# salsa_II_v3a.net
KiCad netlist of a schematic drawn in EAGLE
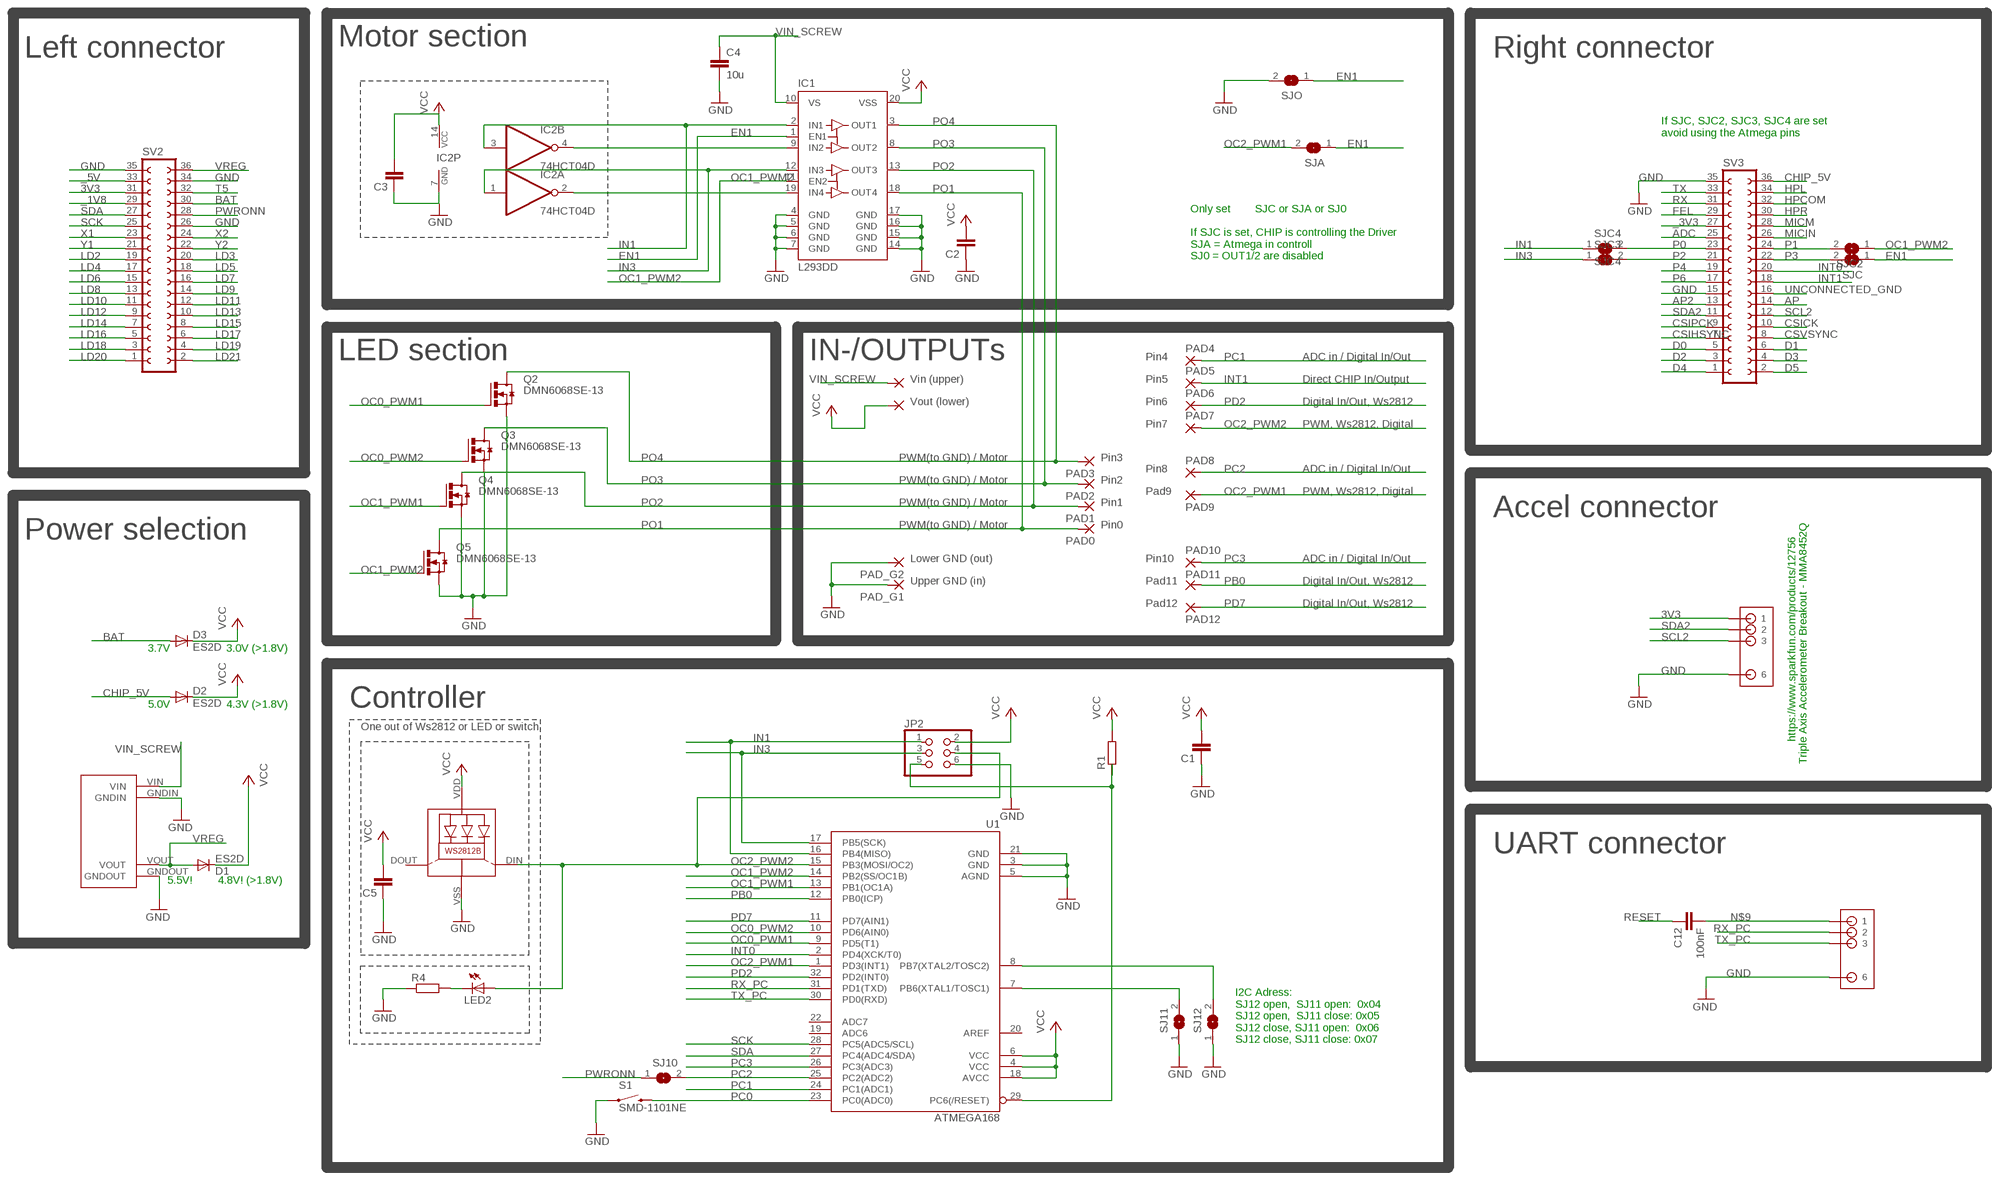
[diagram p0: schematic, sheet 1]

(export (version "E")
  (design (tool "Eeschema 10.0.6"))
  (components
    (comp (ref "C1")
      (value "C-EUC0805")
      (footprint "eagle-import:C0805")
      (libsource (lib "eagle-import") (part "C-EUC0805"))
    )
    (comp (ref "C2")
      (value "C-EUC0805")
      (footprint "eagle-import:C0805")
      (libsource (lib "eagle-import") (part "C-EUC0805"))
    )
    (comp (ref "C3")
      (value "C-EUC0805")
      (footprint "eagle-import:C0805")
      (libsource (lib "eagle-import") (part "C-EUC0805"))
    )
    (comp (ref "C4")
      (value "10u")
      (footprint "eagle-import:C1210")
      (libsource (lib "eagle-import") (part "C-EUC1210"))
    )
    (comp (ref "C5")
      (value "C-EUC0805")
      (footprint "eagle-import:C0805")
      (libsource (lib "eagle-import") (part "C-EUC0805"))
    )
    (comp (ref "C12")
      (value "100nF")
      (footprint "eagle-import:C1206")
      (libsource (lib "eagle-import") (part "C-EUC1206"))
    )
    (comp (ref "D1")
      (value "ES2D")
      (footprint "eagle-import:SMB")
      (libsource (lib "eagle-import") (part "ES2D"))
    )
    (comp (ref "D2")
      (value "ES2D")
      (footprint "eagle-import:SMB")
      (libsource (lib "eagle-import") (part "ES2D"))
    )
    (comp (ref "D3")
      (value "ES2D")
      (footprint "eagle-import:SMB")
      (libsource (lib "eagle-import") (part "ES2D"))
    )
    (comp (ref "IC1")
      (value "L293DD")
      (footprint "eagle-import:SO20")
      (libsource (lib "eagle-import") (part "L293DD"))
    )
    (comp (ref "IC2")
      (value "74HCT04D")
      (footprint "eagle-import:SO14")
      (libsource (lib "eagle-import") (part "7404DHCT"))
    )
    (comp (ref "JP2")
      (value "PINHD-2X3")
      (footprint "eagle-import:2X03")
      (libsource (lib "eagle-import") (part "PINHD-2X3"))
    )
    (comp (ref "LED1")
      (value "WS2812B")
      (footprint "eagle-import:WS2812B")
      (libsource (lib "eagle-import") (part "WS2812B"))
    )
    (comp (ref "LED2")
      (value "LEDCHIP-LED0805")
      (footprint "eagle-import:CHIP-LED0805")
      (libsource (lib "eagle-import") (part "LEDCHIP-LED0805"))
    )
    (comp (ref "PAD0")
      (value "3,17/1,3")
      (footprint "eagle-import:3,17_1,3")
      (libsource (lib "eagle-import") (part "3,17/1,3"))
    )
    (comp (ref "PAD1")
      (value "3,17/1,3")
      (footprint "eagle-import:3,17_1,3")
      (libsource (lib "eagle-import") (part "3,17/1,3"))
    )
    (comp (ref "PAD2")
      (value "3,17/1,3")
      (footprint "eagle-import:3,17_1,3")
      (libsource (lib "eagle-import") (part "3,17/1,3"))
    )
    (comp (ref "PAD3")
      (value "3,17/1,3")
      (footprint "eagle-import:3,17_1,3")
      (libsource (lib "eagle-import") (part "3,17/1,3"))
    )
    (comp (ref "PAD4")
      (value "3,17/1,3")
      (footprint "eagle-import:3,17_1,3")
      (libsource (lib "eagle-import") (part "3,17/1,3"))
    )
    (comp (ref "PAD5")
      (value "3,17/1,3")
      (footprint "eagle-import:3,17_1,3")
      (libsource (lib "eagle-import") (part "3,17/1,3"))
    )
    (comp (ref "PAD6")
      (value "3,17/1,3")
      (footprint "eagle-import:3,17_1,3")
      (libsource (lib "eagle-import") (part "3,17/1,3"))
    )
    (comp (ref "PAD7")
      (value "3,17/1,3")
      (footprint "eagle-import:3,17_1,3")
      (libsource (lib "eagle-import") (part "3,17/1,3"))
    )
    (comp (ref "PAD8")
      (value "3,17/1,3")
      (footprint "eagle-import:3,17_1,3")
      (libsource (lib "eagle-import") (part "3,17/1,3"))
    )
    (comp (ref "PAD9")
      (value "SMD2")
      (footprint "eagle-import:SMD1,27-2,54")
      (libsource (lib "eagle-import") (part "SMD2"))
    )
    (comp (ref "PAD10")
      (value "3,17/1,3")
      (footprint "eagle-import:3,17_1,3")
      (libsource (lib "eagle-import") (part "3,17/1,3"))
    )
    (comp (ref "PAD11")
      (value "WIREPADSMD1,27-254")
      (footprint "eagle-import:SMD1,27-2,54")
      (libsource (lib "eagle-import") (part "WIREPADSMD1,27-254"))
    )
    (comp (ref "PAD12")
      (value "SMD2")
      (footprint "eagle-import:SMD1,27-2,54")
      (libsource (lib "eagle-import") (part "SMD2"))
    )
    (comp (ref "PAD17")
      (value "3,17/1,3")
      (footprint "eagle-import:3,17_1,3")
      (libsource (lib "eagle-import") (part "3,17/1,3"))
    )
    (comp (ref "PAD_G1")
      (value "3,17/1,3")
      (footprint "eagle-import:3,17_1,3")
      (libsource (lib "eagle-import") (part "3,17/1,3"))
    )
    (comp (ref "PAD_G2")
      (value "3,17/1,3")
      (footprint "eagle-import:3,17_1,3")
      (libsource (lib "eagle-import") (part "3,17/1,3"))
    )
    (comp (ref "PAD_VIN")
      (value "3,17/1,3")
      (footprint "eagle-import:3,17_1,3")
      (libsource (lib "eagle-import") (part "3,17/1,3"))
    )
    (comp (ref "Q2")
      (value "DMN6068SE-13")
      (footprint "eagle-import:SOT223")
      (libsource (lib "eagle-import") (part "NMOSFET_SMD_223"))
    )
    (comp (ref "Q3")
      (value "DMN6068SE-13")
      (footprint "eagle-import:SOT223")
      (libsource (lib "eagle-import") (part "NMOSFET_SMD_223"))
    )
    (comp (ref "Q4")
      (value "DMN6068SE-13")
      (footprint "eagle-import:SOT223")
      (libsource (lib "eagle-import") (part "NMOSFET_SMD_223"))
    )
    (comp (ref "Q5")
      (value "DMN6068SE-13")
      (footprint "eagle-import:SOT223")
      (libsource (lib "eagle-import") (part "NMOSFET_SMD_223"))
    )
    (comp (ref "R1")
      (value "R-EU_M1206")
      (footprint "eagle-import:M1206")
      (libsource (lib "eagle-import") (part "R-EU_M1206"))
    )
    (comp (ref "R4")
      (value "R-EU_M1206")
      (footprint "eagle-import:M1206")
      (libsource (lib "eagle-import") (part "R-EU_M1206"))
    )
    (comp (ref "S1")
      (value "SMD-1101NE")
      (footprint "eagle-import:TACTILE-SWITCH-1101NE")
      (libsource (lib "eagle-import") (part "SWITCH-MOMENTARY-2-SMD-1101NE"))
    )
    (comp (ref "SJ10")
      (value "SJ")
      (footprint "eagle-import:SJ")
      (libsource (lib "eagle-import") (part "SJ"))
    )
    (comp (ref "SJ11")
      (value "SJ")
      (footprint "eagle-import:SJ")
      (libsource (lib "eagle-import") (part "SJ"))
    )
    (comp (ref "SJ12")
      (value "SJ")
      (footprint "eagle-import:SJ")
      (libsource (lib "eagle-import") (part "SJ"))
    )
    (comp (ref "SJA") (value "SJ") (footprint "eagle-import:SJ") (libsource (lib "eagle-import") (part "SJ")))
    (comp (ref "SJC") (value "SJ") (footprint "eagle-import:SJ") (libsource (lib "eagle-import") (part "SJ")))
    (comp (ref "SJC2")
      (value "SJ")
      (footprint "eagle-import:SJ")
      (libsource (lib "eagle-import") (part "SJ"))
    )
    (comp (ref "SJC3")
      (value "SJ")
      (footprint "eagle-import:SJ")
      (libsource (lib "eagle-import") (part "SJ"))
    )
    (comp (ref "SJC4")
      (value "SJC4")
      (footprint "eagle-import:SJ")
      (libsource (lib "eagle-import") (part "SJ"))
    )
    (comp (ref "SJO") (value "SJ") (footprint "eagle-import:SJ") (libsource (lib "eagle-import") (part "SJ")))
    (comp (ref "SV2")
      (value "FE18-2")
      (footprint "eagle-import:FE18-2")
      (libsource (lib "eagle-import") (part "FE18-2"))
    )
    (comp (ref "SV3")
      (value "FE18-2")
      (footprint "eagle-import:FE18-2")
      (libsource (lib "eagle-import") (part "FE18-2"))
    )
    (comp (ref "U$1")
      (value "MP1584EN")
      (footprint "eagle-import:MP1584EN")
      (libsource (lib "eagle-import") (part "MP1584EN"))
    )
    (comp (ref "U$3")
      (value "6_TO_4_HEADER")
      (footprint "eagle-import:6_TO_4_HEADER")
      (libsource (lib "eagle-import") (part "6_TO_4_HEADER"))
    )
    (comp (ref "U$4")
      (value "6_TO_4_HEADER")
      (footprint "eagle-import:6_TO_4_HEADER")
      (libsource (lib "eagle-import") (part "6_TO_4_HEADER"))
    )
    (comp (ref "U1")
      (value "ATMEGA168")
      (footprint "eagle-import:TQFP32-08")
      (libsource (lib "eagle-import") (part "ATMEGA168"))
    )
  )
  (nets
    (net (code "1") (name "/3V3") (class "Default")
      (node (ref "SV2") (pin "31") (pinfunction "31_31") (pintype "passive"))
      (node (ref "U$4") (pin "1") (pinfunction "1_1") (pintype "bidirectional"))
    )
    (net (code "2") (name "/ADC") (class "Default")
      (node (ref "SV3") (pin "25") (pinfunction "25_25") (pintype "passive"))
    )
    (net (code "3") (name "/AP") (class "Default")
      (node (ref "SV3") (pin "14") (pinfunction "14_14") (pintype "passive"))
    )
    (net (code "4") (name "/AP2") (class "Default")
      (node (ref "SV3") (pin "13") (pinfunction "13_13") (pintype "passive"))
    )
    (net (code "5") (name "/BAT") (class "Default")
      (node (ref "D3") (pin "A") (pinfunction "A_A") (pintype "passive"))
      (node (ref "SV2") (pin "30") (pinfunction "30_30") (pintype "passive"))
    )
    (net (code "6") (name "/CHIP_5V") (class "Default")
      (node (ref "D2") (pin "A") (pinfunction "A_A") (pintype "passive"))
      (node (ref "SV3") (pin "36") (pinfunction "36_36") (pintype "passive"))
    )
    (net (code "7") (name "/CSICK") (class "Default")
      (node (ref "SV3") (pin "10") (pinfunction "10_10") (pintype "passive"))
    )
    (net (code "8") (name "/CSIHSYNC") (class "Default")
      (node (ref "SV3") (pin "7") (pinfunction "7_7") (pintype "passive"))
    )
    (net (code "9") (name "/CSIPCK") (class "Default")
      (node (ref "SV3") (pin "9") (pinfunction "9_9") (pintype "passive"))
    )
    (net (code "10") (name "/CSVSYNC") (class "Default")
      (node (ref "SV3") (pin "8") (pinfunction "8_8") (pintype "passive"))
    )
    (net (code "11") (name "/D0") (class "Default")
      (node (ref "SV3") (pin "5") (pinfunction "5_5") (pintype "passive"))
    )
    (net (code "12") (name "/D1") (class "Default")
      (node (ref "SV3") (pin "6") (pinfunction "6_6") (pintype "passive"))
    )
    (net (code "13") (name "/D2") (class "Default")
      (node (ref "SV3") (pin "3") (pinfunction "3_3") (pintype "passive"))
    )
    (net (code "14") (name "/D3") (class "Default")
      (node (ref "SV3") (pin "4") (pinfunction "4_4") (pintype "passive"))
    )
    (net (code "15") (name "/D4") (class "Default")
      (node (ref "SV3") (pin "1") (pinfunction "1_1") (pintype "passive"))
    )
    (net (code "16") (name "/D5") (class "Default")
      (node (ref "SV3") (pin "2") (pinfunction "2_2") (pintype "passive"))
    )
    (net (code "17") (name "/EN1") (class "Default")
      (node (ref "IC1") (pin "1") (pinfunction "EN1_1") (pintype "input"))
      (node (ref "SJA") (pin "1") (pinfunction "1_1") (pintype "passive"))
      (node (ref "SJC") (pin "1") (pinfunction "1_1") (pintype "passive"))
      (node (ref "SJO") (pin "1") (pinfunction "1_1") (pintype "passive"))
    )
    (net (code "18") (name "/FEL") (class "Default")
      (node (ref "SV3") (pin "29") (pinfunction "29_29") (pintype "passive"))
    )
    (net (code "19") (name "/HPCOM") (class "Default")
      (node (ref "SV3") (pin "32") (pinfunction "32_32") (pintype "passive"))
    )
    (net (code "20") (name "/HPL") (class "Default")
      (node (ref "SV3") (pin "34") (pinfunction "34_34") (pintype "passive"))
    )
    (net (code "21") (name "/HPR") (class "Default")
      (node (ref "SV3") (pin "30") (pinfunction "30_30") (pintype "passive"))
    )
    (net (code "22") (name "/IN1") (class "Default")
      (node (ref "IC1") (pin "2") (pinfunction "IN1_2") (pintype "input"))
      (node (ref "IC2") (pin "3") (pinfunction "I_3") (pintype "input"))
      (node (ref "JP2") (pin "1") (pinfunction "1_1") (pintype "passive"))
      (node (ref "SJC4") (pin "1") (pinfunction "1_1") (pintype "passive"))
      (node (ref "U1") (pin "16") (pinfunction "PB4(MISO)_16") (pintype "bidirectional"))
    )
    (net (code "23") (name "/IN3") (class "Default")
      (node (ref "IC1") (pin "12") (pinfunction "IN3_12") (pintype "input"))
      (node (ref "IC2") (pin "1") (pinfunction "I_1") (pintype "input"))
      (node (ref "JP2") (pin "3") (pinfunction "3_3") (pintype "passive"))
      (node (ref "SJC3") (pin "1") (pinfunction "1_1") (pintype "passive"))
      (node (ref "U1") (pin "17") (pinfunction "PB5(SCK)_17") (pintype "bidirectional"))
    )
    (net (code "24") (name "/INT0") (class "Default")
      (node (ref "SV3") (pin "20") (pinfunction "20_20") (pintype "passive"))
      (node (ref "U1") (pin "2") (pinfunction "PD4(XCK/T0)_2") (pintype "bidirectional"))
    )
    (net (code "25") (name "/INT1") (class "Default")
      (node (ref "PAD5") (pin "1") (pinfunction "P_1") (pintype "passive"))
      (node (ref "SV3") (pin "18") (pinfunction "18_18") (pintype "passive"))
    )
    (net (code "26") (name "/LD2") (class "Default")
      (node (ref "SV2") (pin "19") (pinfunction "19_19") (pintype "passive"))
    )
    (net (code "27") (name "/LD3") (class "Default")
      (node (ref "SV2") (pin "20") (pinfunction "20_20") (pintype "passive"))
    )
    (net (code "28") (name "/LD4") (class "Default")
      (node (ref "SV2") (pin "17") (pinfunction "17_17") (pintype "passive"))
    )
    (net (code "29") (name "/LD5") (class "Default")
      (node (ref "SV2") (pin "18") (pinfunction "18_18") (pintype "passive"))
    )
    (net (code "30") (name "/LD6") (class "Default")
      (node (ref "SV2") (pin "15") (pinfunction "15_15") (pintype "passive"))
    )
    (net (code "31") (name "/LD7") (class "Default")
      (node (ref "SV2") (pin "16") (pinfunction "16_16") (pintype "passive"))
    )
    (net (code "32") (name "/LD8") (class "Default")
      (node (ref "SV2") (pin "13") (pinfunction "13_13") (pintype "passive"))
    )
    (net (code "33") (name "/LD9") (class "Default")
      (node (ref "SV2") (pin "14") (pinfunction "14_14") (pintype "passive"))
    )
    (net (code "34") (name "/LD10") (class "Default")
      (node (ref "SV2") (pin "11") (pinfunction "11_11") (pintype "passive"))
    )
    (net (code "35") (name "/LD11") (class "Default")
      (node (ref "SV2") (pin "12") (pinfunction "12_12") (pintype "passive"))
    )
    (net (code "36") (name "/LD12") (class "Default")
      (node (ref "SV2") (pin "9") (pinfunction "9_9") (pintype "passive"))
    )
    (net (code "37") (name "/LD13") (class "Default")
      (node (ref "SV2") (pin "10") (pinfunction "10_10") (pintype "passive"))
    )
    (net (code "38") (name "/LD14") (class "Default")
      (node (ref "SV2") (pin "7") (pinfunction "7_7") (pintype "passive"))
    )
    (net (code "39") (name "/LD15") (class "Default")
      (node (ref "SV2") (pin "8") (pinfunction "8_8") (pintype "passive"))
    )
    (net (code "40") (name "/LD16") (class "Default")
      (node (ref "SV2") (pin "5") (pinfunction "5_5") (pintype "passive"))
    )
    (net (code "41") (name "/LD17") (class "Default")
      (node (ref "SV2") (pin "6") (pinfunction "6_6") (pintype "passive"))
    )
    (net (code "42") (name "/LD18") (class "Default")
      (node (ref "SV2") (pin "3") (pinfunction "3_3") (pintype "passive"))
    )
    (net (code "43") (name "/LD19") (class "Default")
      (node (ref "SV2") (pin "4") (pinfunction "4_4") (pintype "passive"))
    )
    (net (code "44") (name "/LD20") (class "Default")
      (node (ref "SV2") (pin "1") (pinfunction "1_1") (pintype "passive"))
    )
    (net (code "45") (name "/LD21") (class "Default")
      (node (ref "SV2") (pin "2") (pinfunction "2_2") (pintype "passive"))
    )
    (net (code "46") (name "/MICIN") (class "Default")
      (node (ref "SV3") (pin "26") (pinfunction "26_26") (pintype "passive"))
    )
    (net (code "47") (name "/MICM") (class "Default")
      (node (ref "SV3") (pin "28") (pinfunction "28_28") (pintype "passive"))
    )
    (net (code "48") (name "/N$9") (class "Default")
      (node (ref "C12") (pin "2") (pinfunction "2_2") (pintype "passive"))
      (node (ref "U$3") (pin "1") (pinfunction "1_1") (pintype "bidirectional"))
    )
    (net (code "49") (name "/OC0_PWM1") (class "Default")
      (node (ref "Q2") (pin "1") (pinfunction "G_1") (pintype "passive"))
      (node (ref "U1") (pin "9") (pinfunction "PD5(T1)_9") (pintype "bidirectional"))
    )
    (net (code "50") (name "/OC0_PWM2") (class "Default")
      (node (ref "Q3") (pin "1") (pinfunction "G_1") (pintype "passive"))
      (node (ref "U1") (pin "10") (pinfunction "PD6(AIN0)_10") (pintype "bidirectional"))
    )
    (net (code "51") (name "/OC1_PWM1") (class "Default")
      (node (ref "Q4") (pin "1") (pinfunction "G_1") (pintype "passive"))
      (node (ref "U1") (pin "13") (pinfunction "PB1(OC1A)_13") (pintype "bidirectional"))
    )
    (net (code "52") (name "/OC1_PWM2") (class "Default")
      (node (ref "IC1") (pin "11") (pinfunction "EN2_11") (pintype "input"))
      (node (ref "Q5") (pin "1") (pinfunction "G_1") (pintype "passive"))
      (node (ref "SJC2") (pin "1") (pinfunction "1_1") (pintype "passive"))
      (node (ref "U1") (pin "14") (pinfunction "PB2(SS/OC1B)_14") (pintype "bidirectional"))
    )
    (net (code "53") (name "/OC2_PWM1") (class "Default")
      (node (ref "PAD9") (pin "1") (pinfunction "P_1") (pintype "passive"))
      (node (ref "SJA") (pin "2") (pinfunction "2_2") (pintype "passive"))
      (node (ref "U1") (pin "1") (pinfunction "PD3(INT1)_1") (pintype "bidirectional"))
    )
    (net (code "54") (name "/OC2_PWM2") (class "Default")
      (node (ref "JP2") (pin "4") (pinfunction "4_4") (pintype "passive"))
      (node (ref "LED1") (pin "DIN") (pinfunction "DI_DIN") (pintype "input"))
      (node (ref "LED2") (pin "A") (pinfunction "A_A") (pintype "passive"))
      (node (ref "PAD7") (pin "1") (pinfunction "P_1") (pintype "passive"))
      (node (ref "U1") (pin "15") (pinfunction "PB3(MOSI/OC2)_15") (pintype "bidirectional"))
    )
    (net (code "55") (name "/P0") (class "Default")
      (node (ref "SJC4") (pin "2") (pinfunction "2_2") (pintype "passive"))
      (node (ref "SV3") (pin "23") (pinfunction "23_23") (pintype "passive"))
    )
    (net (code "56") (name "/P1") (class "Default")
      (node (ref "SJC2") (pin "2") (pinfunction "2_2") (pintype "passive"))
      (node (ref "SV3") (pin "24") (pinfunction "24_24") (pintype "passive"))
    )
    (net (code "57") (name "/P2") (class "Default")
      (node (ref "SJC3") (pin "2") (pinfunction "2_2") (pintype "passive"))
      (node (ref "SV3") (pin "21") (pinfunction "21_21") (pintype "passive"))
    )
    (net (code "58") (name "/P3") (class "Default")
      (node (ref "SJC") (pin "2") (pinfunction "2_2") (pintype "passive"))
      (node (ref "SV3") (pin "22") (pinfunction "22_22") (pintype "passive"))
    )
    (net (code "59") (name "/P4") (class "Default")
      (node (ref "SV3") (pin "19") (pinfunction "19_19") (pintype "passive"))
    )
    (net (code "60") (name "/P6") (class "Default")
      (node (ref "SV3") (pin "17") (pinfunction "17_17") (pintype "passive"))
    )
    (net (code "61") (name "/PB0") (class "Default")
      (node (ref "PAD11") (pin "1") (pinfunction "P_1") (pintype "passive"))
      (node (ref "U1") (pin "12") (pinfunction "PB0(ICP)_12") (pintype "bidirectional"))
    )
    (net (code "62") (name "/PC0") (class "Default")
      (node (ref "S1") (pin "P$2") (pinfunction "2_P$2") (pintype "passive"))
      (node (ref "U1") (pin "23") (pinfunction "PC0(ADC0)_23") (pintype "bidirectional"))
    )
    (net (code "63") (name "/PC1") (class "Default")
      (node (ref "PAD4") (pin "1") (pinfunction "P_1") (pintype "passive"))
      (node (ref "U1") (pin "24") (pinfunction "PC1(ADC1)_24") (pintype "bidirectional"))
    )
    (net (code "64") (name "/PC2") (class "Default")
      (node (ref "PAD8") (pin "1") (pinfunction "P_1") (pintype "passive"))
      (node (ref "SJ10") (pin "2") (pinfunction "2_2") (pintype "passive"))
      (node (ref "U1") (pin "25") (pinfunction "PC2(ADC2)_25") (pintype "bidirectional"))
    )
    (net (code "65") (name "/PC3") (class "Default")
      (node (ref "PAD10") (pin "1") (pinfunction "P_1") (pintype "passive"))
      (node (ref "U1") (pin "26") (pinfunction "PC3(ADC3)_26") (pintype "bidirectional"))
    )
    (net (code "66") (name "/PD2") (class "Default")
      (node (ref "PAD6") (pin "1") (pinfunction "P_1") (pintype "passive"))
      (node (ref "U1") (pin "32") (pinfunction "PD2(INT0)_32") (pintype "bidirectional"))
    )
    (net (code "67") (name "/PD7") (class "Default")
      (node (ref "PAD12") (pin "1") (pinfunction "P_1") (pintype "passive"))
      (node (ref "U1") (pin "11") (pinfunction "PD7(AIN1)_11") (pintype "bidirectional"))
    )
    (net (code "68") (name "/PO1") (class "Default")
      (node (ref "IC1") (pin "18") (pinfunction "OUT4_18") (pintype "output"))
      (node (ref "PAD0") (pin "1") (pinfunction "P_1") (pintype "passive"))
      (node (ref "Q5") (pin "2") (pinfunction "D_2") (pintype "passive"))
      (node (ref "Q5") (pin "4") (pinfunction "D_4") (pintype "passive"))
    )
    (net (code "69") (name "/PO2") (class "Default")
      (node (ref "IC1") (pin "13") (pinfunction "OUT3_13") (pintype "output"))
      (node (ref "PAD1") (pin "1") (pinfunction "P_1") (pintype "passive"))
      (node (ref "Q4") (pin "2") (pinfunction "D_2") (pintype "passive"))
      (node (ref "Q4") (pin "4") (pinfunction "D_4") (pintype "passive"))
    )
    (net (code "70") (name "/PO3") (class "Default")
      (node (ref "IC1") (pin "8") (pinfunction "OUT2_8") (pintype "output"))
      (node (ref "PAD2") (pin "1") (pinfunction "P_1") (pintype "passive"))
      (node (ref "Q3") (pin "2") (pinfunction "D_2") (pintype "passive"))
      (node (ref "Q3") (pin "4") (pinfunction "D_4") (pintype "passive"))
    )
    (net (code "71") (name "/PO4") (class "Default")
      (node (ref "IC1") (pin "3") (pinfunction "OUT1_3") (pintype "output"))
      (node (ref "PAD3") (pin "1") (pinfunction "P_1") (pintype "passive"))
      (node (ref "Q2") (pin "2") (pinfunction "D_2") (pintype "passive"))
      (node (ref "Q2") (pin "4") (pinfunction "D_4") (pintype "passive"))
    )
    (net (code "72") (name "/PWRONN") (class "Default")
      (node (ref "SJ10") (pin "1") (pinfunction "1_1") (pintype "passive"))
      (node (ref "SV2") (pin "28") (pinfunction "28_28") (pintype "passive"))
    )
    (net (code "73") (name "/RESET") (class "Default")
      (node (ref "C12") (pin "1") (pinfunction "1_1") (pintype "passive"))
      (node (ref "JP2") (pin "5") (pinfunction "5_5") (pintype "passive"))
      (node (ref "R1") (pin "1") (pinfunction "1_1") (pintype "passive"))
      (node (ref "U1") (pin "29") (pinfunction "PC6(/RESET)_29") (pintype "bidirectional"))
    )
    (net (code "74") (name "/RX") (class "Default")
      (node (ref "SV3") (pin "31") (pinfunction "31_31") (pintype "passive"))
    )
    (net (code "75") (name "/RX_PC") (class "Default")
      (node (ref "U$3") (pin "2") (pinfunction "2_2") (pintype "bidirectional"))
      (node (ref "U1") (pin "31") (pinfunction "PD1(TXD)_31") (pintype "bidirectional"))
    )
    (net (code "76") (name "/SCK") (class "Default")
      (node (ref "SV2") (pin "25") (pinfunction "25_25") (pintype "passive"))
      (node (ref "U1") (pin "28") (pinfunction "PC5(ADC5/SCL)_28") (pintype "bidirectional"))
    )
    (net (code "77") (name "/SCL2") (class "Default")
      (node (ref "SV3") (pin "12") (pinfunction "12_12") (pintype "passive"))
      (node (ref "U$4") (pin "3") (pinfunction "3_3") (pintype "bidirectional"))
    )
    (net (code "78") (name "/SDA") (class "Default")
      (node (ref "SV2") (pin "27") (pinfunction "27_27") (pintype "passive"))
      (node (ref "U1") (pin "27") (pinfunction "PC4(ADC4/SDA)_27") (pintype "bidirectional"))
    )
    (net (code "79") (name "/SDA2") (class "Default")
      (node (ref "SV3") (pin "11") (pinfunction "11_11") (pintype "passive"))
      (node (ref "U$4") (pin "2") (pinfunction "2_2") (pintype "bidirectional"))
    )
    (net (code "80") (name "/T5") (class "Default")
      (node (ref "SV2") (pin "32") (pinfunction "32_32") (pintype "passive"))
    )
    (net (code "81") (name "/TX") (class "Default")
      (node (ref "SV3") (pin "33") (pinfunction "33_33") (pintype "passive"))
    )
    (net (code "82") (name "/TX_PC") (class "Default")
      (node (ref "U$3") (pin "3") (pinfunction "3_3") (pintype "bidirectional"))
      (node (ref "U1") (pin "30") (pinfunction "PD0(RXD)_30") (pintype "bidirectional"))
    )
    (net (code "83") (name "/UNCONNECTED_GND") (class "Default")
      (node (ref "SV3") (pin "16") (pinfunction "16_16") (pintype "passive"))
    )
    (net (code "84") (name "/VIN_SCREW") (class "Default")
      (node (ref "C4") (pin "1") (pinfunction "1_1") (pintype "passive"))
      (node (ref "IC1") (pin "10") (pinfunction "VS_10") (pintype "power_in"))
      (node (ref "PAD_VIN") (pin "1") (pinfunction "P_1") (pintype "passive"))
      (node (ref "U$1") (pin "VIN") (pinfunction "VIN_VIN") (pintype "power_in"))
    )
    (net (code "85") (name "/VREG") (class "Default")
      (node (ref "D1") (pin "A") (pinfunction "A_A") (pintype "passive"))
      (node (ref "SV2") (pin "36") (pinfunction "36_36") (pintype "passive"))
      (node (ref "U$1") (pin "VOUT") (pinfunction "VOUT_VOUT") (pintype "power_in"))
    )
    (net (code "86") (name "/X1") (class "Default")
      (node (ref "SV2") (pin "23") (pinfunction "23_23") (pintype "passive"))
    )
    (net (code "87") (name "/X2") (class "Default")
      (node (ref "SV2") (pin "24") (pinfunction "24_24") (pintype "passive"))
    )
    (net (code "88") (name "/Y1") (class "Default")
      (node (ref "SV2") (pin "21") (pinfunction "21_21") (pintype "passive"))
    )
    (net (code "89") (name "/Y2") (class "Default")
      (node (ref "SV2") (pin "22") (pinfunction "22_22") (pintype "passive"))
    )
    (net (code "90") (name "/_1V8") (class "Default")
      (node (ref "SV2") (pin "29") (pinfunction "29_29") (pintype "passive"))
    )
    (net (code "91") (name "/_3V3") (class "Default")
      (node (ref "SV3") (pin "27") (pinfunction "27_27") (pintype "passive"))
    )
    (net (code "92") (name "/_5V") (class "Default")
      (node (ref "SV2") (pin "33") (pinfunction "33_33") (pintype "passive"))
    )
    (net (code "93") (name "GND") (class "Default")
      (node (ref "C1") (pin "1") (pinfunction "1_1") (pintype "passive"))
      (node (ref "C2") (pin "1") (pinfunction "1_1") (pintype "passive"))
      (node (ref "C3") (pin "1") (pinfunction "1_1") (pintype "passive"))
      (node (ref "C4") (pin "2") (pinfunction "2_2") (pintype "passive"))
      (node (ref "C5") (pin "1") (pinfunction "1_1") (pintype "passive"))
      (node (ref "IC1") (pin "14") (pinfunction "GND_14") (pintype "power_in"))
      (node (ref "IC1") (pin "15") (pinfunction "GND_15") (pintype "power_in"))
      (node (ref "IC1") (pin "16") (pinfunction "GND_16") (pintype "power_in"))
      (node (ref "IC1") (pin "17") (pinfunction "GND_17") (pintype "power_in"))
      (node (ref "IC1") (pin "4") (pinfunction "GND_4") (pintype "power_in"))
      (node (ref "IC1") (pin "5") (pinfunction "GND_5") (pintype "power_in"))
      (node (ref "IC1") (pin "6") (pinfunction "GND_6") (pintype "power_in"))
      (node (ref "IC1") (pin "7") (pinfunction "GND_7") (pintype "power_in"))
      (node (ref "IC2") (pin "7") (pinfunction "GND_7") (pintype "power_in"))
      (node (ref "JP2") (pin "6") (pinfunction "6_6") (pintype "passive"))
      (node (ref "LED1") (pin "VSS") (pinfunction "GND_VSS") (pintype "power_in"))
      (node (ref "PAD_G1") (pin "1") (pinfunction "P_1") (pintype "passive"))
      (node (ref "PAD_G2") (pin "1") (pinfunction "P_1") (pintype "passive"))
      (node (ref "Q2") (pin "3") (pinfunction "S_3") (pintype "passive"))
      (node (ref "Q3") (pin "3") (pinfunction "S_3") (pintype "passive"))
      (node (ref "Q4") (pin "3") (pinfunction "S_3") (pintype "passive"))
      (node (ref "Q5") (pin "3") (pinfunction "S_3") (pintype "passive"))
      (node (ref "R4") (pin "1") (pinfunction "1_1") (pintype "passive"))
      (node (ref "S1") (pin "P$1") (pinfunction "1_P$1") (pintype "passive"))
      (node (ref "SJ11") (pin "1") (pinfunction "1_1") (pintype "passive"))
      (node (ref "SJ12") (pin "1") (pinfunction "1_1") (pintype "passive"))
      (node (ref "SJO") (pin "2") (pinfunction "2_2") (pintype "passive"))
      (node (ref "SV2") (pin "26") (pinfunction "26_26") (pintype "passive"))
      (node (ref "SV2") (pin "34") (pinfunction "34_34") (pintype "passive"))
      (node (ref "SV2") (pin "35") (pinfunction "35_35") (pintype "passive"))
      (node (ref "SV3") (pin "15") (pinfunction "15_15") (pintype "passive"))
      (node (ref "SV3") (pin "35") (pinfunction "35_35") (pintype "passive"))
      (node (ref "U$1") (pin "GNDIN") (pinfunction "GNDIN_GNDIN") (pintype "power_in"))
      (node (ref "U$1") (pin "GNDOUT") (pinfunction "GNDOUT_GNDOUT") (pintype "power_in"))
      (node (ref "U$3") (pin "6") (pinfunction "6_6") (pintype "bidirectional"))
      (node (ref "U$4") (pin "6") (pinfunction "6_6") (pintype "bidirectional"))
      (node (ref "U1") (pin "21") (pinfunction "GND_21") (pintype "bidirectional"))
      (node (ref "U1") (pin "3") (pinfunction "GND_3") (pintype "bidirectional"))
      (node (ref "U1") (pin "5") (pinfunction "AGND_5") (pintype "bidirectional"))
    )
    (net (code "94") (name "Net-(IC1-IN2)") (class "Default")
      (node (ref "IC1") (pin "9") (pinfunction "IN2_9") (pintype "input"))
      (node (ref "IC2") (pin "4") (pinfunction "O_4") (pintype "output"))
    )
    (net (code "95") (name "Net-(IC1-IN4)") (class "Default")
      (node (ref "IC1") (pin "19") (pinfunction "IN4_19") (pintype "input"))
      (node (ref "IC2") (pin "2") (pinfunction "O_2") (pintype "output"))
    )
    (net (code "96") (name "Net-(LED2-PadC)") (class "Default")
      (node (ref "LED2") (pin "C") (pinfunction "C_C") (pintype "passive"))
      (node (ref "R4") (pin "2") (pinfunction "2_2") (pintype "passive"))
    )
    (net (code "97") (name "Net-(U1-PB6(XTAL1{slash}TOSC1))") (class "Default")
      (node (ref "SJ11") (pin "2") (pinfunction "2_2") (pintype "passive"))
      (node (ref "U1") (pin "7") (pinfunction "PB6(XTAL1/TOSC1)_7") (pintype "bidirectional"))
    )
    (net (code "98") (name "Net-(U1-PB7(XTAL2{slash}TOSC2))") (class "Default")
      (node (ref "SJ12") (pin "2") (pinfunction "2_2") (pintype "passive"))
      (node (ref "U1") (pin "8") (pinfunction "PB7(XTAL2/TOSC2)_8") (pintype "bidirectional"))
    )
    (net (code "99") (name "VCC") (class "Default")
      (node (ref "C1") (pin "2") (pinfunction "2_2") (pintype "passive"))
      (node (ref "C2") (pin "2") (pinfunction "2_2") (pintype "passive"))
      (node (ref "C3") (pin "2") (pinfunction "2_2") (pintype "passive"))
      (node (ref "C5") (pin "2") (pinfunction "2_2") (pintype "passive"))
      (node (ref "D1") (pin "C") (pinfunction "C_C") (pintype "passive"))
      (node (ref "D2") (pin "C") (pinfunction "C_C") (pintype "passive"))
      (node (ref "D3") (pin "C") (pinfunction "C_C") (pintype "passive"))
      (node (ref "IC1") (pin "20") (pinfunction "VSS_20") (pintype "power_in"))
      (node (ref "IC2") (pin "14") (pinfunction "VCC_14") (pintype "power_in"))
      (node (ref "JP2") (pin "2") (pinfunction "2_2") (pintype "passive"))
      (node (ref "LED1") (pin "VDD") (pinfunction "VDD_VDD") (pintype "power_in"))
      (node (ref "PAD17") (pin "1") (pinfunction "P_1") (pintype "passive"))
      (node (ref "R1") (pin "2") (pinfunction "2_2") (pintype "passive"))
      (node (ref "U1") (pin "18") (pinfunction "AVCC_18") (pintype "bidirectional"))
      (node (ref "U1") (pin "4") (pinfunction "VCC_4") (pintype "bidirectional"))
      (node (ref "U1") (pin "6") (pinfunction "VCC_6") (pintype "bidirectional"))
    )
    (net (code "100") (name "unconnected-(LED1-DO-PadDOUT)") (class "Default")
      (node (ref "LED1") (pin "DOUT") (pinfunction "DO_DOUT") (pintype "output"))
    )
    (net (code "101") (name "unconnected-(U1-ADC6-Pad19)") (class "Default")
      (node (ref "U1") (pin "19") (pinfunction "ADC6_19") (pintype "bidirectional"))
    )
    (net (code "102") (name "unconnected-(U1-ADC7-Pad22)") (class "Default")
      (node (ref "U1") (pin "22") (pinfunction "ADC7_22") (pintype "bidirectional"))
    )
    (net (code "103") (name "unconnected-(U1-AREF-Pad20)") (class "Default")
      (node (ref "U1") (pin "20") (pinfunction "AREF_20") (pintype "bidirectional"))
    )
  )
)
